# JTAG_AMC_Box.net
KiCad netlist of a schematic drawn in Altium Designer
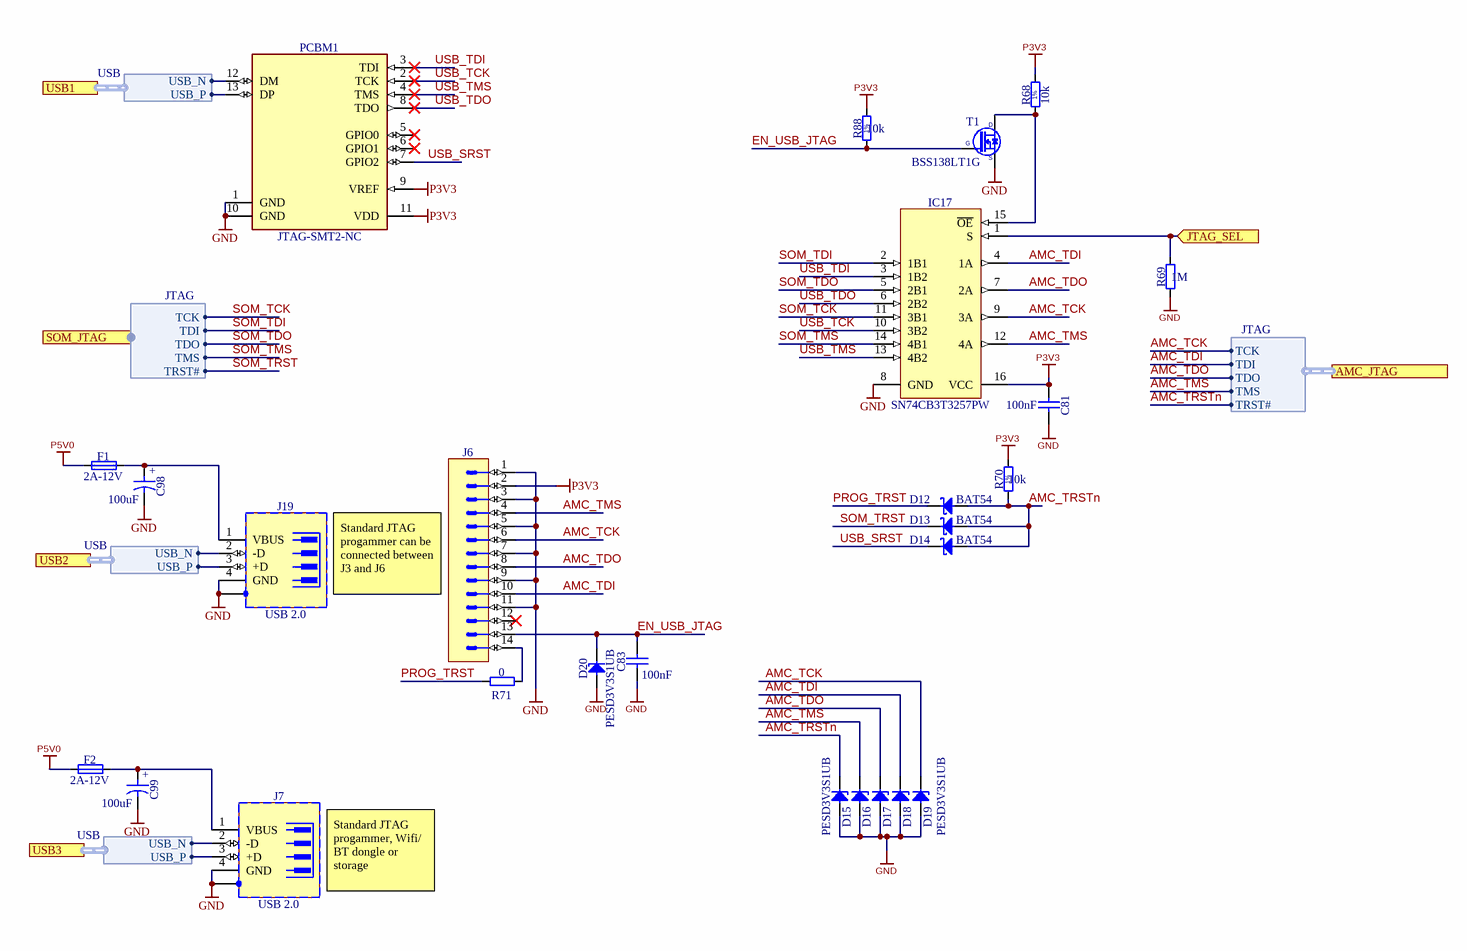
[diagram p0: JTAG_AMC_Box.SchDoc]

(export (version "E")
  (design (tool "Eeschema 10.0.6"))
  (components
    (comp (ref "C81")
      (value "100nF")
      (footprint "CAPC0603X33N")
      (description "Non-polarised capacitor")
      (fields
        (field (name "MANUFACTURER PART NUMBER") "CC0201_100NF_6.3V_10%_X5R")
        (field (name "MANUFACTURER") "GENERIC")
        (field (name "AUTHOR") "CERN DEM JLC")
      )
      (libsource (lib "Capacitors") (part "Capacitor - non polarized"))
    )
    (comp (ref "C83")
      (value "100nF")
      (footprint "CAPC0603X33N")
      (description "Non-polarised capacitor")
      (fields
        (field (name "MANUFACTURER PART NUMBER") "CC0201_100NF_6.3V_10%_X5R")
        (field (name "MANUFACTURER") "GENERIC")
        (field (name "AUTHOR") "CERN DEM JLC")
      )
      (libsource (lib "Capacitors") (part "Capacitor - non polarized"))
    )
    (comp (ref "C98")
      (value "100uF")
      (footprint "CAPAE660X540N")
      (description "Polarised capacitor")
      (fields
        (field (name "PART NUMBER") "CAE660-540_100UF_16V_20%")
        (field (name "VOLTAGE") "16V")
        (field (name "AUTHOR") "CERN DEM JLC")
      )
      (libsource (lib "Capacitors") (part "Capacitor - polarized"))
    )
    (comp (ref "C99")
      (value "100uF")
      (footprint "CAPAE660X540N")
      (description "Polarised capacitor")
      (fields
        (field (name "PART NUMBER") "CAE660-540_100UF_16V_20%")
        (field (name "VOLTAGE") "16V")
        (field (name "AUTHOR") "CERN DEM JLC")
      )
      (libsource (lib "Capacitors") (part "Capacitor - polarized"))
    )
    (comp (ref "D12")
      (value "BAT54")
      (footprint "SOT95P240X130-3N")
      (description "Diode Schottky  Anode Pin 1 Cathode Pin 3 (Pas de pin 2)")
      (fields
        (field (name "VOLTAGE") "30V")
        (field (name "POWER") "200mA")
        (field (name "AUTHOR") "CERN DEM JLC")
      )
      (libsource (lib "ICs And Semiconductors") (part "Diode Schottky A1C3"))
    )
    (comp (ref "D13")
      (value "BAT54")
      (footprint "SOT95P240X130-3N")
      (description "Diode Schottky  Anode Pin 1 Cathode Pin 3 (Pas de pin 2)")
      (fields
        (field (name "VOLTAGE") "30V")
        (field (name "POWER") "200mA")
        (field (name "AUTHOR") "CERN DEM JLC")
      )
      (libsource (lib "ICs And Semiconductors") (part "Diode Schottky A1C3"))
    )
    (comp (ref "D14")
      (value "BAT54")
      (footprint "SOT95P240X130-3N")
      (description "Diode Schottky  Anode Pin 1 Cathode Pin 3 (Pas de pin 2)")
      (fields
        (field (name "VOLTAGE") "30V")
        (field (name "POWER") "200mA")
        (field (name "AUTHOR") "CERN DEM JLC")
      )
      (libsource (lib "ICs And Semiconductors") (part "Diode Schottky A1C3"))
    )
    (comp (ref "D15")
      (value "PESD3V3S1UB")
      (footprint "SODFL1608X65N")
      (description "ESD protection diode")
      (fields
        (field (name "MANUFACTURER PART NUMBER") "ESD8351XV2T1G")
        (field (name "MANUFACTURER") "NXP SEMICONDUCTORS")
        (field (name "AUTHOR") "CERN DEM JLC")
      )
      (libsource (lib "ICs And Semiconductors") (part "Diode ESD"))
    )
    (comp (ref "D16")
      (value "PESD3V3S1UB")
      (footprint "SODFL1608X65N")
      (description "ESD protection diode")
      (fields
        (field (name "MANUFACTURER PART NUMBER") "ESD8351XV2T1G")
        (field (name "MANUFACTURER") "NXP SEMICONDUCTORS")
        (field (name "AUTHOR") "CERN DEM JLC")
      )
      (libsource (lib "ICs And Semiconductors") (part "Diode ESD"))
    )
    (comp (ref "D17")
      (value "PESD3V3S1UB")
      (footprint "SODFL1608X65N")
      (description "ESD protection diode")
      (fields
        (field (name "MANUFACTURER PART NUMBER") "ESD8351XV2T1G")
        (field (name "MANUFACTURER") "NXP SEMICONDUCTORS")
        (field (name "AUTHOR") "CERN DEM JLC")
      )
      (libsource (lib "ICs And Semiconductors") (part "Diode ESD"))
    )
    (comp (ref "D18")
      (value "PESD3V3S1UB")
      (footprint "SODFL1608X65N")
      (description "ESD protection diode")
      (fields
        (field (name "MANUFACTURER PART NUMBER") "ESD8351XV2T1G")
        (field (name "MANUFACTURER") "NXP SEMICONDUCTORS")
        (field (name "AUTHOR") "CERN DEM JLC")
      )
      (libsource (lib "ICs And Semiconductors") (part "Diode ESD"))
    )
    (comp (ref "D19")
      (value "PESD3V3S1UB")
      (footprint "SODFL1608X65N")
      (description "ESD protection diode")
      (fields
        (field (name "MANUFACTURER PART NUMBER") "ESD8351XV2T1G")
        (field (name "MANUFACTURER") "NXP SEMICONDUCTORS")
        (field (name "AUTHOR") "CERN DEM JLC")
      )
      (libsource (lib "ICs And Semiconductors") (part "Diode ESD"))
    )
    (comp (ref "D20")
      (value "PESD3V3S1UB")
      (footprint "SODFL1608X65N")
      (description "ESD protection diode")
      (fields
        (field (name "MANUFACTURER PART NUMBER") "ESD8351XV2T1G")
        (field (name "MANUFACTURER") "NXP SEMICONDUCTORS")
        (field (name "AUTHOR") "CERN DEM JLC")
      )
      (libsource (lib "ICs And Semiconductors") (part "Diode ESD"))
    )
    (comp (ref "F1")
      (value "2A-12V")
      (footprint "FUSR_LITTELFUSE_1812L200")
      (description "Fuse")
      (fields
        (field (name "PART NUMBER") "FUSR1812_LITTELFUSE_1812L200/12")
        (field (name "MANUFACTURER") "LITTELFUSE")
        (field (name "AUTHOR") "CERN DEM BC")
      )
      (libsource (lib "Eletro-mechanical") (part "Fuse"))
    )
    (comp (ref "F2")
      (value "2A-12V")
      (footprint "FUSR_LITTELFUSE_1812L200")
      (description "Fuse")
      (fields
        (field (name "PART NUMBER") "FUSR1812_LITTELFUSE_1812L200/12")
        (field (name "MANUFACTURER") "LITTELFUSE")
        (field (name "AUTHOR") "CERN DEM BC")
      )
      (libsource (lib "Eletro-mechanical") (part "Fuse"))
    )
    (comp (ref "IC17")
      (value "SN74CB3T3257PW")
      (footprint "SOP65P640X120-16N")
      (description "4-BIT 1-OF-2 FET Multiplexer/Demultiplexer 2.5V/3.3V Low-Voltage Bus Switch 5V Tolerant Shifter")
      (fields (field (name "MANUFACTURER") "TEXAS INSTRUMENTS") (field (name "AUTHOR") "CERN DEM JLC"))
      (libsource (lib "ICs And Semiconductors") (part "743257"))
    )
    (comp (ref "J6")
      (value "Milli-Grid™")
      (footprint "MOLEX_87832-1420")
      (description "Connector 14 Male")
      (fields
        (field (name "PART NUMBER") "MOLEX_87832-1420")
        (field (name "MANUFACTURER") "MOLEX")
        (field (name "AUTHOR") "CERN DEM JLC")
      )
      (libsource (lib "Connectors") (part "Connector 14 Male"))
    )
    (comp (ref "J7")
      (value "USB 2.0")
      (footprint "TYCO_1734366-1")
      (description "4 Pin + 1 Shield USB Receptacle")
      (fields
        (field (name "PART NUMBER") "TYCO_1734366-1")
        (field (name "MANUFACTURER") "TYCO ELECTRONICS")
        (field (name "AUTHOR") "CERN DEM MR")
      )
      (libsource (lib "Connectors") (part "Connector USB 4 Pin + 1Shield"))
    )
    (comp (ref "J19")
      (value "USB 2.0")
      (footprint "TYCO_292303-1")
      (description "4 Pin + 1 Shield USB Receptacle")
      (fields
        (field (name "PART NUMBER") "TYCO_292303-1")
        (field (name "MANUFACTURER") "TYCO ELECTRONICS")
        (field (name "AUTHOR") "CERN DEM JMW")
      )
      (libsource (lib "Connectors") (part "Connector USB 4 Pin + 1Shield"))
    )
    (comp (ref "PCBM1")
      (value "JTAG-SMT2-NC")
      (footprint "PCBM_DIGILENT_JTAG-SMT2-NC")
      (description "Programming Module for Xilinx FPGAs")
      (fields
        (field (name "PART NUMBER") "PCBM_DIGILENT_JTAG-SMT2")
        (field (name "MANUFACTURER") "DIGILENT")
        (field (name "AUTHOR") "GK")
      )
      (libsource (lib "Modules") (part "PCBM_DIGILENT_JTAG-SMT2-NC"))
    )
    (comp (ref "R68")
      (value "10k")
      (footprint "RESC1005X40N")
      (description "Resistor - 1%")
      (fields
        (field (name "MANUFACTURER PART NUMBER") "R0402_10K_1%_0.0625W_100PPM")
        (field (name "MANUFACTURER") "GENERIC")
        (field (name "AUTHOR") "CERN DEM JLC")
      )
      (libsource (lib "Resistors") (part "Resistor - 1%"))
    )
    (comp (ref "R69")
      (value "1M")
      (footprint "RESC1005X40N")
      (description "Resistor - 1%")
      (fields
        (field (name "MANUFACTURER PART NUMBER") "R0402_1M_1%_0.0625W_100PPM")
        (field (name "MANUFACTURER") "GENERIC")
        (field (name "AUTHOR") "CERN DEM JLC")
      )
      (libsource (lib "Resistors") (part "Resistor - 1%"))
    )
    (comp (ref "R70")
      (value "10k")
      (footprint "RESC1005X40N")
      (description "Resistor - 1%")
      (fields
        (field (name "MANUFACTURER PART NUMBER") "R0402_10K_1%_0.0625W_100PPM")
        (field (name "MANUFACTURER") "GENERIC")
        (field (name "AUTHOR") "CERN DEM JLC")
      )
      (libsource (lib "Resistors") (part "Resistor - 1%"))
    )
    (comp (ref "R71")
      (value "0")
      (footprint "RESC1005X40N")
      (description "Resistor")
      (fields
        (field (name "MANUFACTURER PART NUMBER") "R0402_0R_JUMPER")
        (field (name "MANUFACTURER") "GENERIC")
        (field (name "AUTHOR") "CERN DEM JLC")
      )
      (libsource (lib "Resistors") (part "Resistor"))
    )
    (comp (ref "R88")
      (value "10k")
      (footprint "RESC1005X40N")
      (description "Resistor - 1%")
      (fields
        (field (name "MANUFACTURER PART NUMBER") "R0402_10K_1%_0.0625W_100PPM")
        (field (name "MANUFACTURER") "GENERIC")
        (field (name "AUTHOR") "CERN DEM JLC")
      )
      (libsource (lib "Resistors") (part "Resistor - 1%"))
    )
    (comp (ref "T1")
      (value "BSS138LT1G")
      (footprint "SOT95P240X110-3N")
      (description "N-CHANNEL MOSFET WITH DIODE")
      (fields (field (name "MANUFACTURER") "ON SEMICONDUCTOR") (field (name "AUTHOR") "CERN DEM JLC"))
      (libsource (lib "ICs And Semiconductors") (part "N-MOSFET-D 1G 2S 3D"))
    )
  )
  (nets
    (net (code "3") (name "/AMC_TCK") (class "Default")
      (node (ref "D19") (pin "1") (pinfunction "C_1") (pintype "passive"))
      (node (ref "IC17") (pin "9") (pinfunction "3A_9") (pintype "output"))
      (node (ref "J6") (pin "6") (pinfunction "6_6") (pintype "bidirectional"))
    )
    (net (code "4") (name "/AMC_TDI") (class "Default")
      (node (ref "D18") (pin "1") (pinfunction "C_1") (pintype "passive"))
      (node (ref "IC17") (pin "4") (pinfunction "1A_4") (pintype "output"))
      (node (ref "J6") (pin "10") (pinfunction "10_10") (pintype "bidirectional"))
    )
    (net (code "5") (name "/AMC_TDO") (class "Default")
      (node (ref "D17") (pin "1") (pinfunction "C_1") (pintype "passive"))
      (node (ref "IC17") (pin "7") (pinfunction "2A_7") (pintype "output"))
      (node (ref "J6") (pin "8") (pinfunction "8_8") (pintype "bidirectional"))
    )
    (net (code "6") (name "/AMC_TMS") (class "Default")
      (node (ref "D16") (pin "1") (pinfunction "C_1") (pintype "passive"))
      (node (ref "IC17") (pin "12") (pinfunction "4A_12") (pintype "output"))
      (node (ref "J6") (pin "4") (pinfunction "4_4") (pintype "bidirectional"))
    )
    (net (code "7") (name "/AMC_TRSTn") (class "Default")
      (node (ref "D12") (pin "1") (pinfunction "A_1") (pintype "passive"))
      (node (ref "D13") (pin "1") (pinfunction "A_1") (pintype "passive"))
      (node (ref "D14") (pin "1") (pinfunction "A_1") (pintype "passive"))
      (node (ref "D15") (pin "1") (pinfunction "C_1") (pintype "passive"))
      (node (ref "R70") (pin "1") (pinfunction "1_1") (pintype "passive"))
    )
    (net (code "8") (name "/EN_USB_JTAG") (class "Default")
      (node (ref "C83") (pin "2") (pinfunction "2_2") (pintype "passive"))
      (node (ref "D20") (pin "1") (pinfunction "C_1") (pintype "passive"))
      (node (ref "J6") (pin "13") (pinfunction "13_13") (pintype "bidirectional"))
      (node (ref "R88") (pin "1") (pinfunction "1_1") (pintype "passive"))
      (node (ref "T1") (pin "1") (pinfunction "G_1") (pintype "passive"))
    )
    (net (code "9") (name "/JTAG_SEL") (class "Default")
      (node (ref "IC17") (pin "1") (pinfunction "S_1") (pintype "input"))
      (node (ref "R69") (pin "2") (pinfunction "2_2") (pintype "passive"))
    )
    (net (code "10") (name "/PROG_TRST") (class "Default")
      (node (ref "D12") (pin "3") (pinfunction "C_3") (pintype "passive"))
      (node (ref "R71") (pin "2") (pinfunction "2_2") (pintype "passive"))
    )
    (net (code "11") (name "/SOM_TCK") (class "Default")
      (node (ref "IC17") (pin "11") (pinfunction "3B1_11") (pintype "input"))
    )
    (net (code "12") (name "/SOM_TDI") (class "Default")
      (node (ref "IC17") (pin "2") (pinfunction "1B1_2") (pintype "input"))
    )
    (net (code "13") (name "/SOM_TDO") (class "Default")
      (node (ref "IC17") (pin "5") (pinfunction "2B1_5") (pintype "input"))
    )
    (net (code "14") (name "/SOM_TMS") (class "Default")
      (node (ref "IC17") (pin "14") (pinfunction "4B1_14") (pintype "input"))
    )
    (net (code "15") (name "/SOM_TRST") (class "Default")
      (node (ref "D13") (pin "3") (pinfunction "C_3") (pintype "passive"))
    )
    (net (code "16") (name "/USB_SRST") (class "Default")
      (node (ref "D14") (pin "3") (pinfunction "C_3") (pintype "passive"))
      (node (ref "PCBM1") (pin "7") (pinfunction "GPIO2_7") (pintype "bidirectional"))
    )
    (net (code "17") (name "/USB_TCK") (class "Default")
      (node (ref "IC17") (pin "10") (pinfunction "3B2_10") (pintype "input"))
      (node (ref "PCBM1") (pin "2") (pinfunction "TCK_2") (pintype "input"))
    )
    (net (code "18") (name "/USB_TDI") (class "Default")
      (node (ref "IC17") (pin "3") (pinfunction "1B2_3") (pintype "input"))
      (node (ref "PCBM1") (pin "3") (pinfunction "TDI_3") (pintype "input"))
    )
    (net (code "19") (name "/USB_TDO") (class "Default")
      (node (ref "IC17") (pin "6") (pinfunction "2B2_6") (pintype "input"))
      (node (ref "PCBM1") (pin "8") (pinfunction "TDO_8") (pintype "output"))
    )
    (net (code "20") (name "/USB_TMS") (class "Default")
      (node (ref "IC17") (pin "13") (pinfunction "4B2_13") (pintype "input"))
      (node (ref "PCBM1") (pin "4") (pinfunction "TMS_4") (pintype "input"))
    )
    (net (code "23") (name "GND") (class "Default")
      (node (ref "C81") (pin "1") (pinfunction "1_1") (pintype "passive"))
      (node (ref "C83") (pin "1") (pinfunction "1_1") (pintype "passive"))
      (node (ref "C98") (pin "2") (pinfunction "2_2") (pintype "passive"))
      (node (ref "C99") (pin "2") (pinfunction "2_2") (pintype "passive"))
      (node (ref "D15") (pin "2") (pinfunction "A_2") (pintype "passive"))
      (node (ref "D16") (pin "2") (pinfunction "A_2") (pintype "passive"))
      (node (ref "D17") (pin "2") (pinfunction "A_2") (pintype "passive"))
      (node (ref "D18") (pin "2") (pinfunction "A_2") (pintype "passive"))
      (node (ref "D19") (pin "2") (pinfunction "A_2") (pintype "passive"))
      (node (ref "D20") (pin "2") (pinfunction "A_2") (pintype "passive"))
      (node (ref "IC17") (pin "8") (pinfunction "GND_8") (pintype "power_in"))
      (node (ref "J19") (pin "4") (pinfunction "GND_4") (pintype "power_in"))
      (node (ref "J19") (pin "5") (pinfunction "SHIELD_5") (pintype "power_in"))
      (node (ref "J6") (pin "1") (pinfunction "1_1") (pintype "bidirectional"))
      (node (ref "J6") (pin "11") (pinfunction "11_11") (pintype "bidirectional"))
      (node (ref "J6") (pin "3") (pinfunction "3_3") (pintype "bidirectional"))
      (node (ref "J6") (pin "5") (pinfunction "5_5") (pintype "bidirectional"))
      (node (ref "J6") (pin "7") (pinfunction "7_7") (pintype "bidirectional"))
      (node (ref "J6") (pin "9") (pinfunction "9_9") (pintype "bidirectional"))
      (node (ref "J7") (pin "4") (pinfunction "GND_4") (pintype "power_in"))
      (node (ref "J7") (pin "5") (pinfunction "SHIELD_5") (pintype "power_in"))
      (node (ref "PCBM1") (pin "1") (pinfunction "GND_1") (pintype "power_in"))
      (node (ref "PCBM1") (pin "10") (pinfunction "GND_10") (pintype "power_in"))
      (node (ref "R69") (pin "1") (pinfunction "1_1") (pintype "passive"))
      (node (ref "T1") (pin "2") (pinfunction "S_2") (pintype "passive"))
    )
    (net (code "24") (name "Net-(IC17-~{OE})") (class "Default")
      (node (ref "IC17") (pin "15") (pinfunction "~{OE}_15") (pintype "input"))
      (node (ref "R68") (pin "1") (pinfunction "1_1") (pintype "passive"))
      (node (ref "T1") (pin "3") (pinfunction "D_3") (pintype "passive"))
    )
    (net (code "25") (name "Net-(J6-Pad14)") (class "Default")
      (node (ref "J6") (pin "14") (pinfunction "14_14") (pintype "bidirectional"))
      (node (ref "R71") (pin "1") (pinfunction "1_1") (pintype "passive"))
    )
    (net (code "26") (name "Net-(J7-VBUS)") (class "Default")
      (node (ref "C99") (pin "1") (pinfunction "1_1") (pintype "passive"))
      (node (ref "F2") (pin "2") (pinfunction "2_2") (pintype "passive"))
      (node (ref "J7") (pin "1") (pinfunction "VBUS_1") (pintype "power_in"))
    )
    (net (code "27") (name "Net-(J19-VBUS)") (class "Default")
      (node (ref "C98") (pin "1") (pinfunction "1_1") (pintype "passive"))
      (node (ref "F1") (pin "2") (pinfunction "2_2") (pintype "passive"))
      (node (ref "J19") (pin "1") (pinfunction "VBUS_1") (pintype "power_in"))
    )
    (net (code "28") (name "P3V3") (class "Default")
      (node (ref "C81") (pin "2") (pinfunction "2_2") (pintype "passive"))
      (node (ref "IC17") (pin "16") (pinfunction "VCC_16") (pintype "power_in"))
      (node (ref "J6") (pin "2") (pinfunction "2_2") (pintype "bidirectional"))
      (node (ref "PCBM1") (pin "11") (pinfunction "VDD_11") (pintype "power_in"))
      (node (ref "PCBM1") (pin "9") (pinfunction "VREF_9") (pintype "input"))
      (node (ref "R68") (pin "2") (pinfunction "2_2") (pintype "passive"))
      (node (ref "R70") (pin "2") (pinfunction "2_2") (pintype "passive"))
      (node (ref "R88") (pin "2") (pinfunction "2_2") (pintype "passive"))
    )
    (net (code "29") (name "P5V0") (class "Default")
      (node (ref "F1") (pin "1") (pinfunction "1_1") (pintype "passive"))
      (node (ref "F2") (pin "1") (pinfunction "1_1") (pintype "passive"))
    )
    (net (code "30") (name "unconnected-(J6-Pad12)") (class "Default")
      (node (ref "J6") (pin "12") (pinfunction "12_12") (pintype "bidirectional+no_connect"))
    )
    (net (code "31") (name "unconnected-(J7-+D-Pad3)") (class "Default")
      (node (ref "J7") (pin "3") (pinfunction "+D_3") (pintype "bidirectional"))
    )
    (net (code "32") (name "unconnected-(J7--D-Pad2)") (class "Default")
      (node (ref "J7") (pin "2") (pinfunction "-D_2") (pintype "bidirectional"))
    )
    (net (code "33") (name "unconnected-(J19-+D-Pad3)") (class "Default")
      (node (ref "J19") (pin "3") (pinfunction "+D_3") (pintype "bidirectional"))
    )
    (net (code "34") (name "unconnected-(J19--D-Pad2)") (class "Default")
      (node (ref "J19") (pin "2") (pinfunction "-D_2") (pintype "bidirectional"))
    )
    (net (code "35") (name "unconnected-(PCBM1-DM-Pad12)") (class "Default")
      (node (ref "PCBM1") (pin "12") (pinfunction "DM_12") (pintype "bidirectional"))
    )
    (net (code "36") (name "unconnected-(PCBM1-DP-Pad13)") (class "Default")
      (node (ref "PCBM1") (pin "13") (pinfunction "DP_13") (pintype "bidirectional"))
    )
    (net (code "37") (name "unconnected-(PCBM1-GPIO0-Pad5)") (class "Default")
      (node (ref "PCBM1") (pin "5") (pinfunction "GPIO0_5") (pintype "bidirectional+no_connect"))
    )
    (net (code "38") (name "unconnected-(PCBM1-GPIO1-Pad6)") (class "Default")
      (node (ref "PCBM1") (pin "6") (pinfunction "GPIO1_6") (pintype "bidirectional+no_connect"))
    )
  )
)
